# sensor.net
KiCad netlist of a schematic drawn in EAGLE
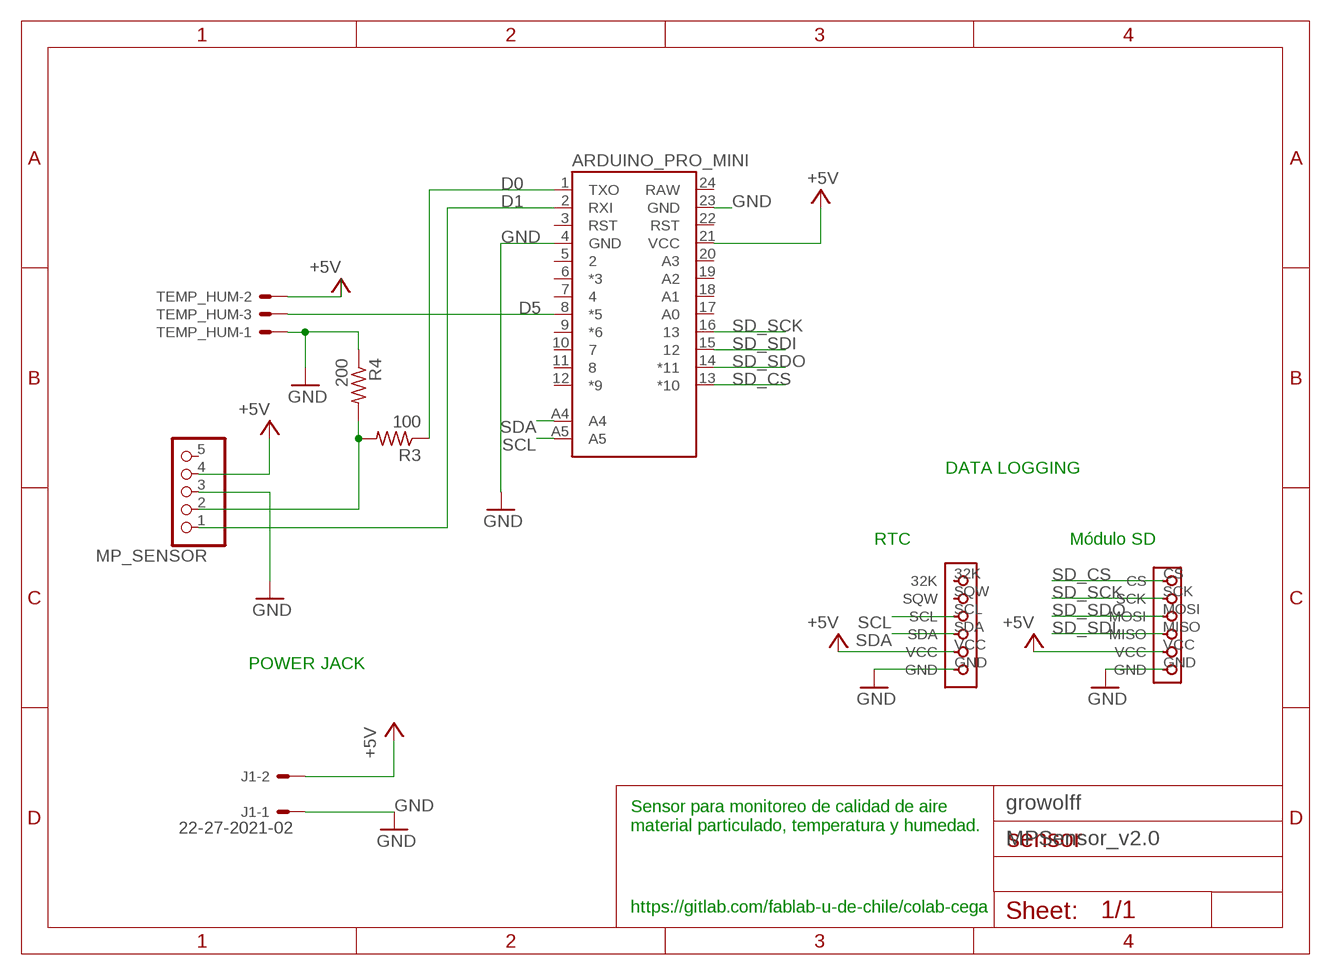
[diagram p0: schematic, sheet 1]

(export (version "E")
  (design (tool "Eeschema 10.0.6"))
  (components
    (comp (ref "ARDUINO_PRO_MINI")
      (value "PRO_MINI_CEGAPRO_MINI_MOD")
      (footprint "eagle-import:ARDUINO_PRO_MINI_MOD")
      (libsource (lib "eagle-import") (part "PRO_MINI_CEGAPRO_MINI_MOD"))
    )
    (comp (ref "J1")
      (value "22-27-2021-02")
      (footprint "eagle-import:6410-02")
      (fields (field (name "MF") "MOLEX"))
      (libsource (lib "eagle-import") (part "22-?-0227-2021"))
    )
    (comp (ref "MP_SENSOR")
      (value "PINHD-1X5")
      (footprint "eagle-import:1X05")
      (libsource (lib "eagle-import") (part "PINHD-1X5"))
    )
    (comp (ref "R3")
      (value "100")
      (footprint "eagle-import:0207_7")
      (libsource (lib "eagle-import") (part "R-US_0207/7"))
    )
    (comp (ref "R4")
      (value "200")
      (footprint "eagle-import:0207_7")
      (libsource (lib "eagle-import") (part "R-US_0207/7"))
    )
    (comp (ref "RTC")
      (value "DS3231_RTC")
      (footprint "eagle-import:DS3231_RTC")
      (libsource (lib "eagle-import") (part "DS3231_RTC"))
    )
    (comp (ref "SD_READER")
      (value "MICRO_SD_READER")
      (footprint "eagle-import:MICRO_SD_READER")
      (libsource (lib "eagle-import") (part "MICRO_SD_READER"))
    )
    (comp (ref "TEMP_HUM")
      (value "22-27-2031-03")
      (footprint "eagle-import:6410-03")
      (fields (field (name "MF") "MOLEX"))
      (libsource (lib "eagle-import") (part "22-?-0327-2031"))
    )
  )
  (nets
    (net (code "1") (name "+5V") (class "Default")
      (node (ref "ARDUINO_PRO_MINI") (pin "21") (pinfunction "VCC_21") (pintype "power_in"))
      (node (ref "J1") (pin "2") (pinfunction "S_2") (pintype "passive"))
      (node (ref "MP_SENSOR") (pin "4") (pinfunction "4_4") (pintype "passive"))
      (node (ref "RTC") (pin "VCC") (pinfunction "VCC_VCC") (pintype "bidirectional"))
      (node (ref "SD_READER") (pin "VCC") (pinfunction "VCC_VCC") (pintype "bidirectional"))
      (node (ref "TEMP_HUM") (pin "2") (pinfunction "S_2") (pintype "passive"))
    )
    (net (code "2") (name "/D0") (class "Default")
      (node (ref "ARDUINO_PRO_MINI") (pin "1") (pinfunction "TXO_1") (pintype "bidirectional"))
      (node (ref "R3") (pin "1") (pinfunction "1_1") (pintype "passive"))
    )
    (net (code "3") (name "/D1") (class "Default")
      (node (ref "ARDUINO_PRO_MINI") (pin "2") (pinfunction "RXI_2") (pintype "bidirectional"))
      (node (ref "MP_SENSOR") (pin "1") (pinfunction "1_1") (pintype "passive"))
    )
    (net (code "4") (name "/D5") (class "Default")
      (node (ref "ARDUINO_PRO_MINI") (pin "8") (pinfunction "*5_8") (pintype "bidirectional"))
      (node (ref "TEMP_HUM") (pin "3") (pinfunction "S_3") (pintype "passive"))
    )
    (net (code "5") (name "/RAW") (class "Default")
      (node (ref "ARDUINO_PRO_MINI") (pin "24") (pinfunction "RAW_24") (pintype "power_in"))
    )
    (net (code "6") (name "/SCL") (class "Default")
      (node (ref "ARDUINO_PRO_MINI") (pin "A5") (pinfunction "A5_A5") (pintype "bidirectional"))
      (node (ref "RTC") (pin "SCL") (pinfunction "SCL_SCL") (pintype "bidirectional"))
    )
    (net (code "7") (name "/SDA") (class "Default")
      (node (ref "ARDUINO_PRO_MINI") (pin "A4") (pinfunction "A4_A4") (pintype "bidirectional"))
      (node (ref "RTC") (pin "SDA") (pinfunction "SDA_SDA") (pintype "bidirectional"))
    )
    (net (code "8") (name "/SD_CS") (class "Default")
      (node (ref "ARDUINO_PRO_MINI") (pin "13") (pinfunction "*10_13") (pintype "bidirectional"))
      (node (ref "SD_READER") (pin "CS") (pinfunction "CS_CS") (pintype "bidirectional"))
    )
    (net (code "9") (name "/SD_SCK") (class "Default")
      (node (ref "ARDUINO_PRO_MINI") (pin "16") (pinfunction "13_16") (pintype "bidirectional"))
      (node (ref "SD_READER") (pin "SCK") (pinfunction "SCK_SCK") (pintype "bidirectional"))
    )
    (net (code "10") (name "/SD_SDI") (class "Default")
      (node (ref "ARDUINO_PRO_MINI") (pin "15") (pinfunction "12_15") (pintype "bidirectional"))
      (node (ref "SD_READER") (pin "MISO") (pinfunction "MISO_MISO") (pintype "bidirectional"))
    )
    (net (code "11") (name "/SD_SDO") (class "Default")
      (node (ref "ARDUINO_PRO_MINI") (pin "14") (pinfunction "*11_14") (pintype "bidirectional"))
      (node (ref "SD_READER") (pin "MOSI") (pinfunction "MOSI_MOSI") (pintype "bidirectional"))
    )
    (net (code "12") (name "GND") (class "Default")
      (node (ref "ARDUINO_PRO_MINI") (pin "23") (pinfunction "GND_23") (pintype "power_in"))
      (node (ref "ARDUINO_PRO_MINI") (pin "4") (pinfunction "GND_4") (pintype "power_in"))
      (node (ref "J1") (pin "1") (pinfunction "S_1") (pintype "passive"))
      (node (ref "MP_SENSOR") (pin "3") (pinfunction "3_3") (pintype "passive"))
      (node (ref "R4") (pin "1") (pinfunction "1_1") (pintype "passive"))
      (node (ref "RTC") (pin "GND") (pinfunction "GND_GND") (pintype "bidirectional"))
      (node (ref "SD_READER") (pin "GND") (pinfunction "GND_GND") (pintype "bidirectional"))
      (node (ref "TEMP_HUM") (pin "1") (pinfunction "S_1") (pintype "passive"))
    )
    (net (code "13") (name "Net-(MP_SENSOR-Pad2)") (class "Default")
      (node (ref "MP_SENSOR") (pin "2") (pinfunction "2_2") (pintype "passive"))
      (node (ref "R3") (pin "2") (pinfunction "2_2") (pintype "passive"))
      (node (ref "R4") (pin "2") (pinfunction "2_2") (pintype "passive"))
    )
    (net (code "14") (name "unconnected-(ARDUINO_PRO_MINI-*3-Pad6)") (class "Default")
      (node (ref "ARDUINO_PRO_MINI") (pin "6") (pinfunction "*3_6") (pintype "bidirectional"))
    )
    (net (code "15") (name "unconnected-(ARDUINO_PRO_MINI-*6-Pad9)") (class "Default")
      (node (ref "ARDUINO_PRO_MINI") (pin "9") (pinfunction "*6_9") (pintype "bidirectional"))
    )
    (net (code "16") (name "unconnected-(ARDUINO_PRO_MINI-*9-Pad12)") (class "Default")
      (node (ref "ARDUINO_PRO_MINI") (pin "12") (pinfunction "*9_12") (pintype "bidirectional"))
    )
    (net (code "17") (name "unconnected-(ARDUINO_PRO_MINI-2-Pad5)") (class "Default")
      (node (ref "ARDUINO_PRO_MINI") (pin "5") (pinfunction "2_5") (pintype "bidirectional"))
    )
    (net (code "18") (name "unconnected-(ARDUINO_PRO_MINI-4-Pad7)") (class "Default")
      (node (ref "ARDUINO_PRO_MINI") (pin "7") (pinfunction "4_7") (pintype "bidirectional"))
    )
    (net (code "19") (name "unconnected-(ARDUINO_PRO_MINI-7-Pad10)") (class "Default")
      (node (ref "ARDUINO_PRO_MINI") (pin "10") (pinfunction "7_10") (pintype "bidirectional"))
    )
    (net (code "20") (name "unconnected-(ARDUINO_PRO_MINI-8-Pad11)") (class "Default")
      (node (ref "ARDUINO_PRO_MINI") (pin "11") (pinfunction "8_11") (pintype "bidirectional"))
    )
    (net (code "21") (name "unconnected-(ARDUINO_PRO_MINI-A0-Pad17)") (class "Default")
      (node (ref "ARDUINO_PRO_MINI") (pin "17") (pinfunction "A0_17") (pintype "bidirectional"))
    )
    (net (code "22") (name "unconnected-(ARDUINO_PRO_MINI-A1-Pad18)") (class "Default")
      (node (ref "ARDUINO_PRO_MINI") (pin "18") (pinfunction "A1_18") (pintype "bidirectional"))
    )
    (net (code "23") (name "unconnected-(ARDUINO_PRO_MINI-A2-Pad19)") (class "Default")
      (node (ref "ARDUINO_PRO_MINI") (pin "19") (pinfunction "A2_19") (pintype "bidirectional"))
    )
    (net (code "24") (name "unconnected-(ARDUINO_PRO_MINI-A3-Pad20)") (class "Default")
      (node (ref "ARDUINO_PRO_MINI") (pin "20") (pinfunction "A3_20") (pintype "bidirectional"))
    )
    (net (code "25") (name "unconnected-(ARDUINO_PRO_MINI-RST-Pad3)") (class "Default")
      (node (ref "ARDUINO_PRO_MINI") (pin "3") (pinfunction "RST_3") (pintype "bidirectional"))
    )
    (net (code "26") (name "unconnected-(ARDUINO_PRO_MINI-RST-Pad22)") (class "Default")
      (node (ref "ARDUINO_PRO_MINI") (pin "22") (pinfunction "RST_22") (pintype "bidirectional"))
    )
    (net (code "27") (name "unconnected-(MP_SENSOR-Pad5)") (class "Default")
      (node (ref "MP_SENSOR") (pin "5") (pinfunction "5_5") (pintype "passive"))
    )
    (net (code "28") (name "unconnected-(RTC-Pad32K)") (class "Default")
      (node (ref "RTC") (pin "32K") (pinfunction "32K_32K") (pintype "bidirectional"))
    )
    (net (code "29") (name "unconnected-(RTC-PadSQW)") (class "Default")
      (node (ref "RTC") (pin "SQW") (pinfunction "SQW_SQW") (pintype "bidirectional"))
    )
  )
)
